# EbotSunny-v02.net
KiCad netlist of a schematic drawn in EAGLE
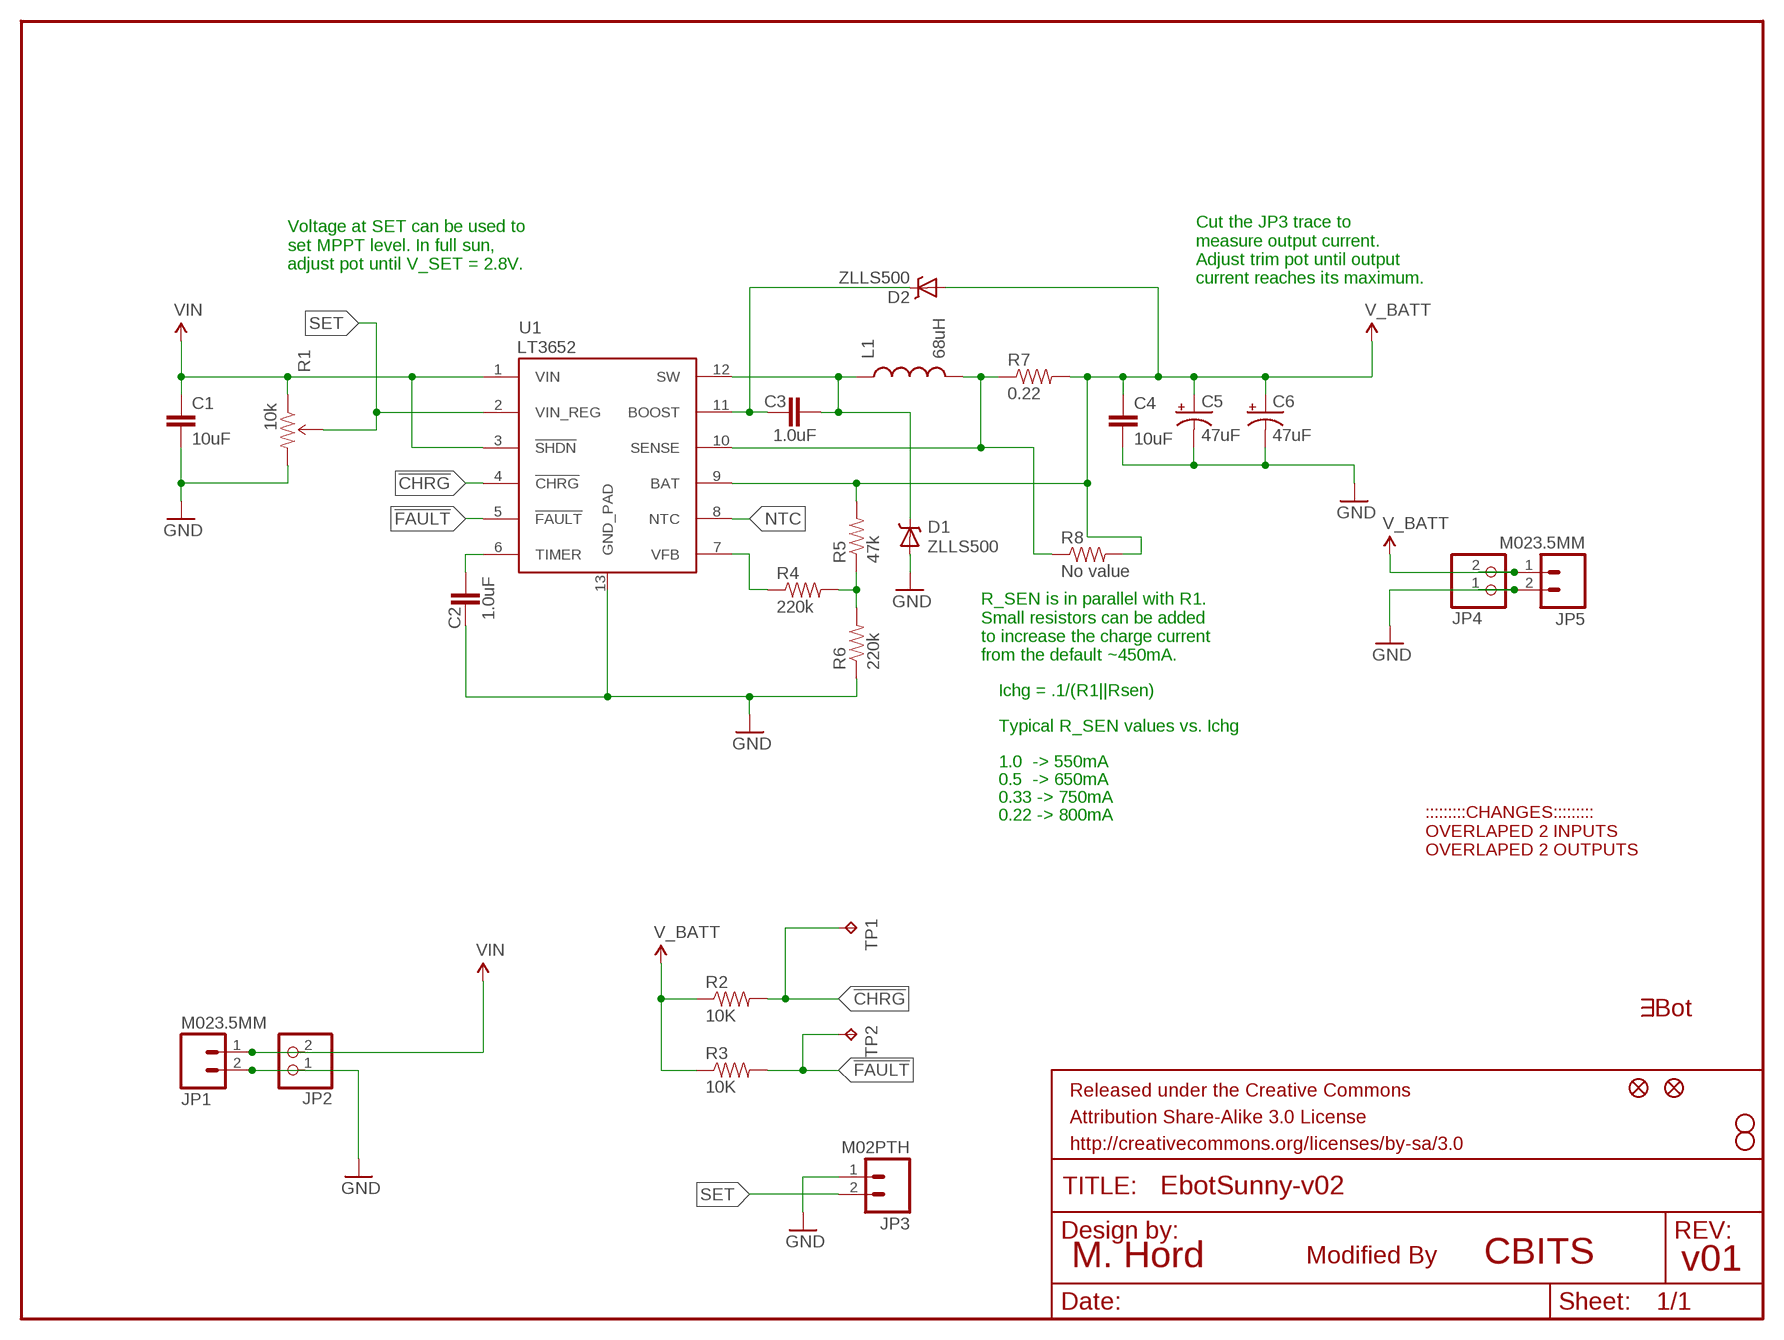
[diagram p0: schematic, sheet 1]

(export (version "E")
  (design (tool "Eeschema 10.0.6"))
  (components
    (comp (ref "C1")
      (value "10uF")
      (footprint "eagle-import:1210")
      (libsource (lib "eagle-import") (part "10UF50V20%(1210)"))
    )
    (comp (ref "C2")
      (value "1.0uF")
      (footprint "eagle-import:0603-CAP")
      (libsource (lib "eagle-import") (part "1.0UF-16V-10%(0603)"))
    )
    (comp (ref "C3")
      (value "1.0uF")
      (footprint "eagle-import:0603-CAP")
      (libsource (lib "eagle-import") (part "1.0UF-16V-10%(0603)"))
    )
    (comp (ref "C4")
      (value "10uF")
      (footprint "eagle-import:1206")
      (libsource (lib "eagle-import") (part "10UF-6.3V-20%(1206)"))
    )
    (comp (ref "C5")
      (value "47uF")
      (footprint "eagle-import:EIA3528")
      (libsource (lib "eagle-import") (part "47UF-TANT"))
    )
    (comp (ref "C6")
      (value "47uF")
      (footprint "eagle-import:EIA3528")
      (libsource (lib "eagle-import") (part "47UF-TANT"))
    )
    (comp (ref "D1")
      (value "ZLLS500")
      (footprint "eagle-import:SOT23")
      (libsource (lib "eagle-import") (part "ZLLS500ZLLS500"))
    )
    (comp (ref "D2")
      (value "ZLLS500")
      (footprint "eagle-import:SOT23")
      (libsource (lib "eagle-import") (part "ZLLS500ZLLS500"))
    )
    (comp (ref "EBOT_LOGO3")
      (value "EBOT_NAME_6MM")
      (footprint "eagle-import:EBOT_NAME_6MM")
      (libsource (lib "eagle-import") (part "EBOT_NAME_6MM"))
    )
    (comp (ref "FID1")
      (value "FIDUCIAL1X2")
      (footprint "eagle-import:FIDUCIAL-1X2")
      (libsource (lib "eagle-import") (part "FIDUCIAL1X2"))
    )
    (comp (ref "FID2")
      (value "FIDUCIAL1X2")
      (footprint "eagle-import:FIDUCIAL-1X2")
      (libsource (lib "eagle-import") (part "FIDUCIAL1X2"))
    )
    (comp (ref "FRAME1")
      (value "FRAME-LETTER")
      (footprint "eagle-import:CREATIVE_COMMONS")
      (libsource (lib "eagle-import") (part "FRAME-LETTER"))
    )
    (comp (ref "JP1")
      (value "M023.5MM")
      (footprint "eagle-import:SCREWTERMINAL-3.5MM-2")
      (libsource (lib "eagle-import") (part "M023.5MM"))
    )
    (comp (ref "JP2")
      (value "PINHD-1X2")
      (footprint "eagle-import:1X02")
      (libsource (lib "eagle-import") (part "PINHD-1X2"))
    )
    (comp (ref "JP3")
      (value "M02PTH")
      (footprint "eagle-import:1X02")
      (libsource (lib "eagle-import") (part "M02PTH"))
    )
    (comp (ref "JP4")
      (value "PINHD-1X2")
      (footprint "eagle-import:1X02")
      (libsource (lib "eagle-import") (part "PINHD-1X2"))
    )
    (comp (ref "JP5")
      (value "M023.5MM")
      (footprint "eagle-import:SCREWTERMINAL-3.5MM-2")
      (libsource (lib "eagle-import") (part "M023.5MM"))
    )
    (comp (ref "L1")
      (value "68uH")
      (footprint "eagle-import:CR75")
      (libsource (lib "eagle-import") (part "INDUCTOR68UH-1A"))
    )
    (comp (ref "R1")
      (value "10k")
      (footprint "eagle-import:TRIMPOT-3MM")
      (libsource (lib "eagle-import") (part "TRIMPOTRES-09285"))
    )
    (comp (ref "R2")
      (value "10K")
      (footprint "eagle-import:0603-RES")
      (libsource (lib "eagle-import") (part "10KOHM1/10W1%(0603)0603"))
    )
    (comp (ref "R3")
      (value "10K")
      (footprint "eagle-import:0603-RES")
      (libsource (lib "eagle-import") (part "10KOHM1/10W1%(0603)0603"))
    )
    (comp (ref "R4")
      (value "220k")
      (footprint "eagle-import:0603-RES")
      (libsource (lib "eagle-import") (part "220KOHM1/10W1%(0603)"))
    )
    (comp (ref "R5")
      (value "47k")
      (footprint "eagle-import:0603-RES")
      (libsource (lib "eagle-import") (part "47KOHM1/10W1%(0603)"))
    )
    (comp (ref "R6")
      (value "220k")
      (footprint "eagle-import:0603-RES")
      (libsource (lib "eagle-import") (part "220KOHM1/10W1%(0603)"))
    )
    (comp (ref "R7")
      (value "0.22")
      (footprint "eagle-import:0805")
      (libsource (lib "eagle-import") (part "0.22OHM1/4W1%(0805)"))
    )
    (comp (ref "R8")
      (value "No value")
      (footprint "eagle-import:0805")
      (libsource (lib "eagle-import") (part "0.22OHM1/4W1%(0805)"))
    )
    (comp (ref "STANDOFF1")
      (value "STAND-OFF")
      (footprint "eagle-import:STAND-OFF")
      (libsource (lib "eagle-import") (part "STAND-OFF"))
    )
    (comp (ref "STANDOFF2")
      (value "STAND-OFF")
      (footprint "eagle-import:STAND-OFF")
      (libsource (lib "eagle-import") (part "STAND-OFF"))
    )
    (comp (ref "TP1")
      (value "TPB1,27")
      (footprint "eagle-import:B1,27")
      (libsource (lib "eagle-import") (part "TPB1,27"))
    )
    (comp (ref "TP2")
      (value "TPB1,27")
      (footprint "eagle-import:B1,27")
      (libsource (lib "eagle-import") (part "TPB1,27"))
    )
    (comp (ref "U1")
      (value "LT3652")
      (footprint "eagle-import:MSOP-12_GND")
      (libsource (lib "eagle-import") (part "LT3652"))
    )
  )
  (nets
    (net (code "1") (name "/~{CHRG}") (class "Default")
      (node (ref "R2") (pin "2") (pinfunction "2_2") (pintype "passive"))
      (node (ref "TP1") (pin "TP") (pinfunction "TP_TP") (pintype "input"))
      (node (ref "U1") (pin "4") (pinfunction "~{CHRG}_4") (pintype "bidirectional"))
    )
    (net (code "2") (name "/~{FAULT}") (class "Default")
      (node (ref "R3") (pin "2") (pinfunction "2_2") (pintype "passive"))
      (node (ref "TP2") (pin "TP") (pinfunction "TP_TP") (pintype "input"))
      (node (ref "U1") (pin "5") (pinfunction "~{FAULT}_5") (pintype "bidirectional"))
    )
    (net (code "3") (name "GND") (class "Default")
      (node (ref "C1") (pin "2") (pinfunction "2_2") (pintype "passive"))
      (node (ref "C2") (pin "1") (pinfunction "1_1") (pintype "passive"))
      (node (ref "C4") (pin "2") (pinfunction "2_2") (pintype "passive"))
      (node (ref "C5") (pin "C") (pinfunction "-_C") (pintype "passive"))
      (node (ref "C6") (pin "C") (pinfunction "-_C") (pintype "passive"))
      (node (ref "D1") (pin "1") (pinfunction "A_1") (pintype "passive"))
      (node (ref "JP1") (pin "2") (pinfunction "2_2") (pintype "passive"))
      (node (ref "JP2") (pin "1") (pinfunction "1_1") (pintype "passive"))
      (node (ref "JP3") (pin "1") (pinfunction "1_1") (pintype "passive"))
      (node (ref "JP4") (pin "1") (pinfunction "1_1") (pintype "passive"))
      (node (ref "JP5") (pin "2") (pinfunction "2_2") (pintype "passive"))
      (node (ref "R1") (pin "3") (pinfunction "CW_3") (pintype "passive"))
      (node (ref "R6") (pin "1") (pinfunction "1_1") (pintype "passive"))
      (node (ref "U1") (pin "13") (pinfunction "GND_PAD_13") (pintype "bidirectional"))
    )
    (net (code "4") (name "NTC") (class "Default")
      (node (ref "U1") (pin "8") (pinfunction "NTC_8") (pintype "bidirectional"))
    )
    (net (code "5") (name "Net-(D1-C)") (class "Default")
      (node (ref "C3") (pin "2") (pinfunction "2_2") (pintype "passive"))
      (node (ref "D1") (pin "3") (pinfunction "C_3") (pintype "passive"))
      (node (ref "L1") (pin "P$1") (pinfunction "1_P$1") (pintype "passive"))
      (node (ref "U1") (pin "12") (pinfunction "SW_12") (pintype "bidirectional"))
    )
    (net (code "6") (name "Net-(D2-C)") (class "Default")
      (node (ref "C3") (pin "1") (pinfunction "1_1") (pintype "passive"))
      (node (ref "D2") (pin "3") (pinfunction "C_3") (pintype "passive"))
      (node (ref "U1") (pin "11") (pinfunction "BOOST_11") (pintype "bidirectional"))
    )
    (net (code "7") (name "Net-(L1-2)") (class "Default")
      (node (ref "L1") (pin "P$2") (pinfunction "2_P$2") (pintype "passive"))
      (node (ref "R7") (pin "1") (pinfunction "1_1") (pintype "passive"))
      (node (ref "R8") (pin "1") (pinfunction "1_1") (pintype "passive"))
      (node (ref "U1") (pin "10") (pinfunction "SENSE_10") (pintype "bidirectional"))
    )
    (net (code "8") (name "Net-(R4-Pad2)") (class "Default")
      (node (ref "R4") (pin "2") (pinfunction "2_2") (pintype "passive"))
      (node (ref "R5") (pin "1") (pinfunction "1_1") (pintype "passive"))
      (node (ref "R6") (pin "2") (pinfunction "2_2") (pintype "passive"))
    )
    (net (code "9") (name "Net-(U1-TIMER)") (class "Default")
      (node (ref "C2") (pin "2") (pinfunction "2_2") (pintype "passive"))
      (node (ref "U1") (pin "6") (pinfunction "TIMER_6") (pintype "bidirectional"))
    )
    (net (code "10") (name "Net-(U1-VFB)") (class "Default")
      (node (ref "R4") (pin "1") (pinfunction "1_1") (pintype "passive"))
      (node (ref "U1") (pin "7") (pinfunction "VFB_7") (pintype "bidirectional"))
    )
    (net (code "11") (name "SET") (class "Default")
      (node (ref "JP3") (pin "2") (pinfunction "2_2") (pintype "passive"))
      (node (ref "R1") (pin "2") (pinfunction "WIPER_2") (pintype "passive"))
      (node (ref "U1") (pin "2") (pinfunction "VIN_REG_2") (pintype "bidirectional"))
    )
    (net (code "12") (name "VIN") (class "Default")
      (node (ref "C1") (pin "1") (pinfunction "1_1") (pintype "passive"))
      (node (ref "JP1") (pin "1") (pinfunction "1_1") (pintype "passive"))
      (node (ref "JP2") (pin "2") (pinfunction "2_2") (pintype "passive"))
      (node (ref "R1") (pin "1") (pinfunction "CCW_1") (pintype "passive"))
      (node (ref "U1") (pin "1") (pinfunction "VIN_1") (pintype "bidirectional"))
      (node (ref "U1") (pin "3") (pinfunction "~{SHDN}_3") (pintype "bidirectional"))
    )
    (net (code "13") (name "V_BATT") (class "Default")
      (node (ref "C4") (pin "1") (pinfunction "1_1") (pintype "passive"))
      (node (ref "C5") (pin "A") (pinfunction "+_A") (pintype "passive"))
      (node (ref "C6") (pin "A") (pinfunction "+_A") (pintype "passive"))
      (node (ref "D2") (pin "1") (pinfunction "A_1") (pintype "passive"))
      (node (ref "JP4") (pin "2") (pinfunction "2_2") (pintype "passive"))
      (node (ref "JP5") (pin "1") (pinfunction "1_1") (pintype "passive"))
      (node (ref "R2") (pin "1") (pinfunction "1_1") (pintype "passive"))
      (node (ref "R3") (pin "1") (pinfunction "1_1") (pintype "passive"))
      (node (ref "R5") (pin "2") (pinfunction "2_2") (pintype "passive"))
      (node (ref "R7") (pin "2") (pinfunction "2_2") (pintype "passive"))
      (node (ref "R8") (pin "2") (pinfunction "2_2") (pintype "passive"))
      (node (ref "U1") (pin "9") (pinfunction "BAT_9") (pintype "bidirectional"))
    )
  )
)
